# LM1117_5V0_to_3V3_LDO.net
KiCad netlist of a schematic drawn in Altium Designer
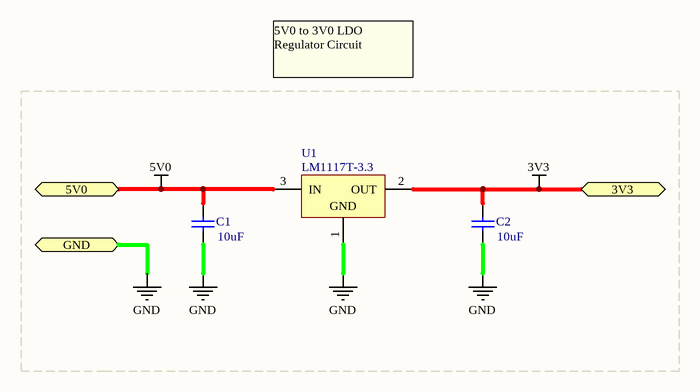
[diagram p0: LM1117 5V0 to 3V3 LDO.SchDoc]

(export (version "E")
  (design (tool "Eeschema 10.0.6"))
  (components
    (comp (ref "C1")
      (value "10uF")
      (footprint "RAD-0.3")
      (description "Capacitor")
      (fields (field (name "Comment") "Cap") (field (name "PUBLISHER") "Altium Limited"))
      (libsource (lib "Miscellaneous Devices") (part "Cap"))
    )
    (comp (ref "C2")
      (value "10uF")
      (footprint "RAD-0.3")
      (description "Capacitor")
      (fields (field (name "Comment") "Cap") (field (name "PUBLISHER") "Altium Limited"))
      (libsource (lib "Miscellaneous Devices") (part "Cap"))
    )
    (comp (ref "U1")
      (value "LM1117T-3.3")
      (footprint "T03B")
      (description "800mA Low-Dropout Linear Regulator, 3-pin TO-220")
      (fields (field (name "MANUFACTURER") "National Semiconductor"))
      (libsource (lib "Altium Content Vault") (part "PM-REG-LM1086-SIL3"))
    )
  )
  (nets
    (net (code "1") (name "3V3") (class "Default")
      (node (ref "C2") (pin "2") (pinfunction "2_2") (pintype "passive"))
      (node (ref "U1") (pin "2") (pinfunction "OUT_2") (pintype "power_in"))
    )
    (net (code "2") (name "5V0") (class "Default")
      (node (ref "C1") (pin "2") (pinfunction "2_2") (pintype "passive"))
      (node (ref "U1") (pin "3") (pinfunction "IN_3") (pintype "power_in"))
    )
    (net (code "3") (name "GND") (class "Default")
      (node (ref "C1") (pin "1") (pinfunction "1_1") (pintype "passive"))
      (node (ref "C2") (pin "1") (pinfunction "1_1") (pintype "passive"))
      (node (ref "U1") (pin "1") (pinfunction "GND_1") (pintype "power_in"))
    )
  )
)
